# YarnControl_Driver_v1_0.net
KiCad netlist of a schematic drawn in Altium Designer
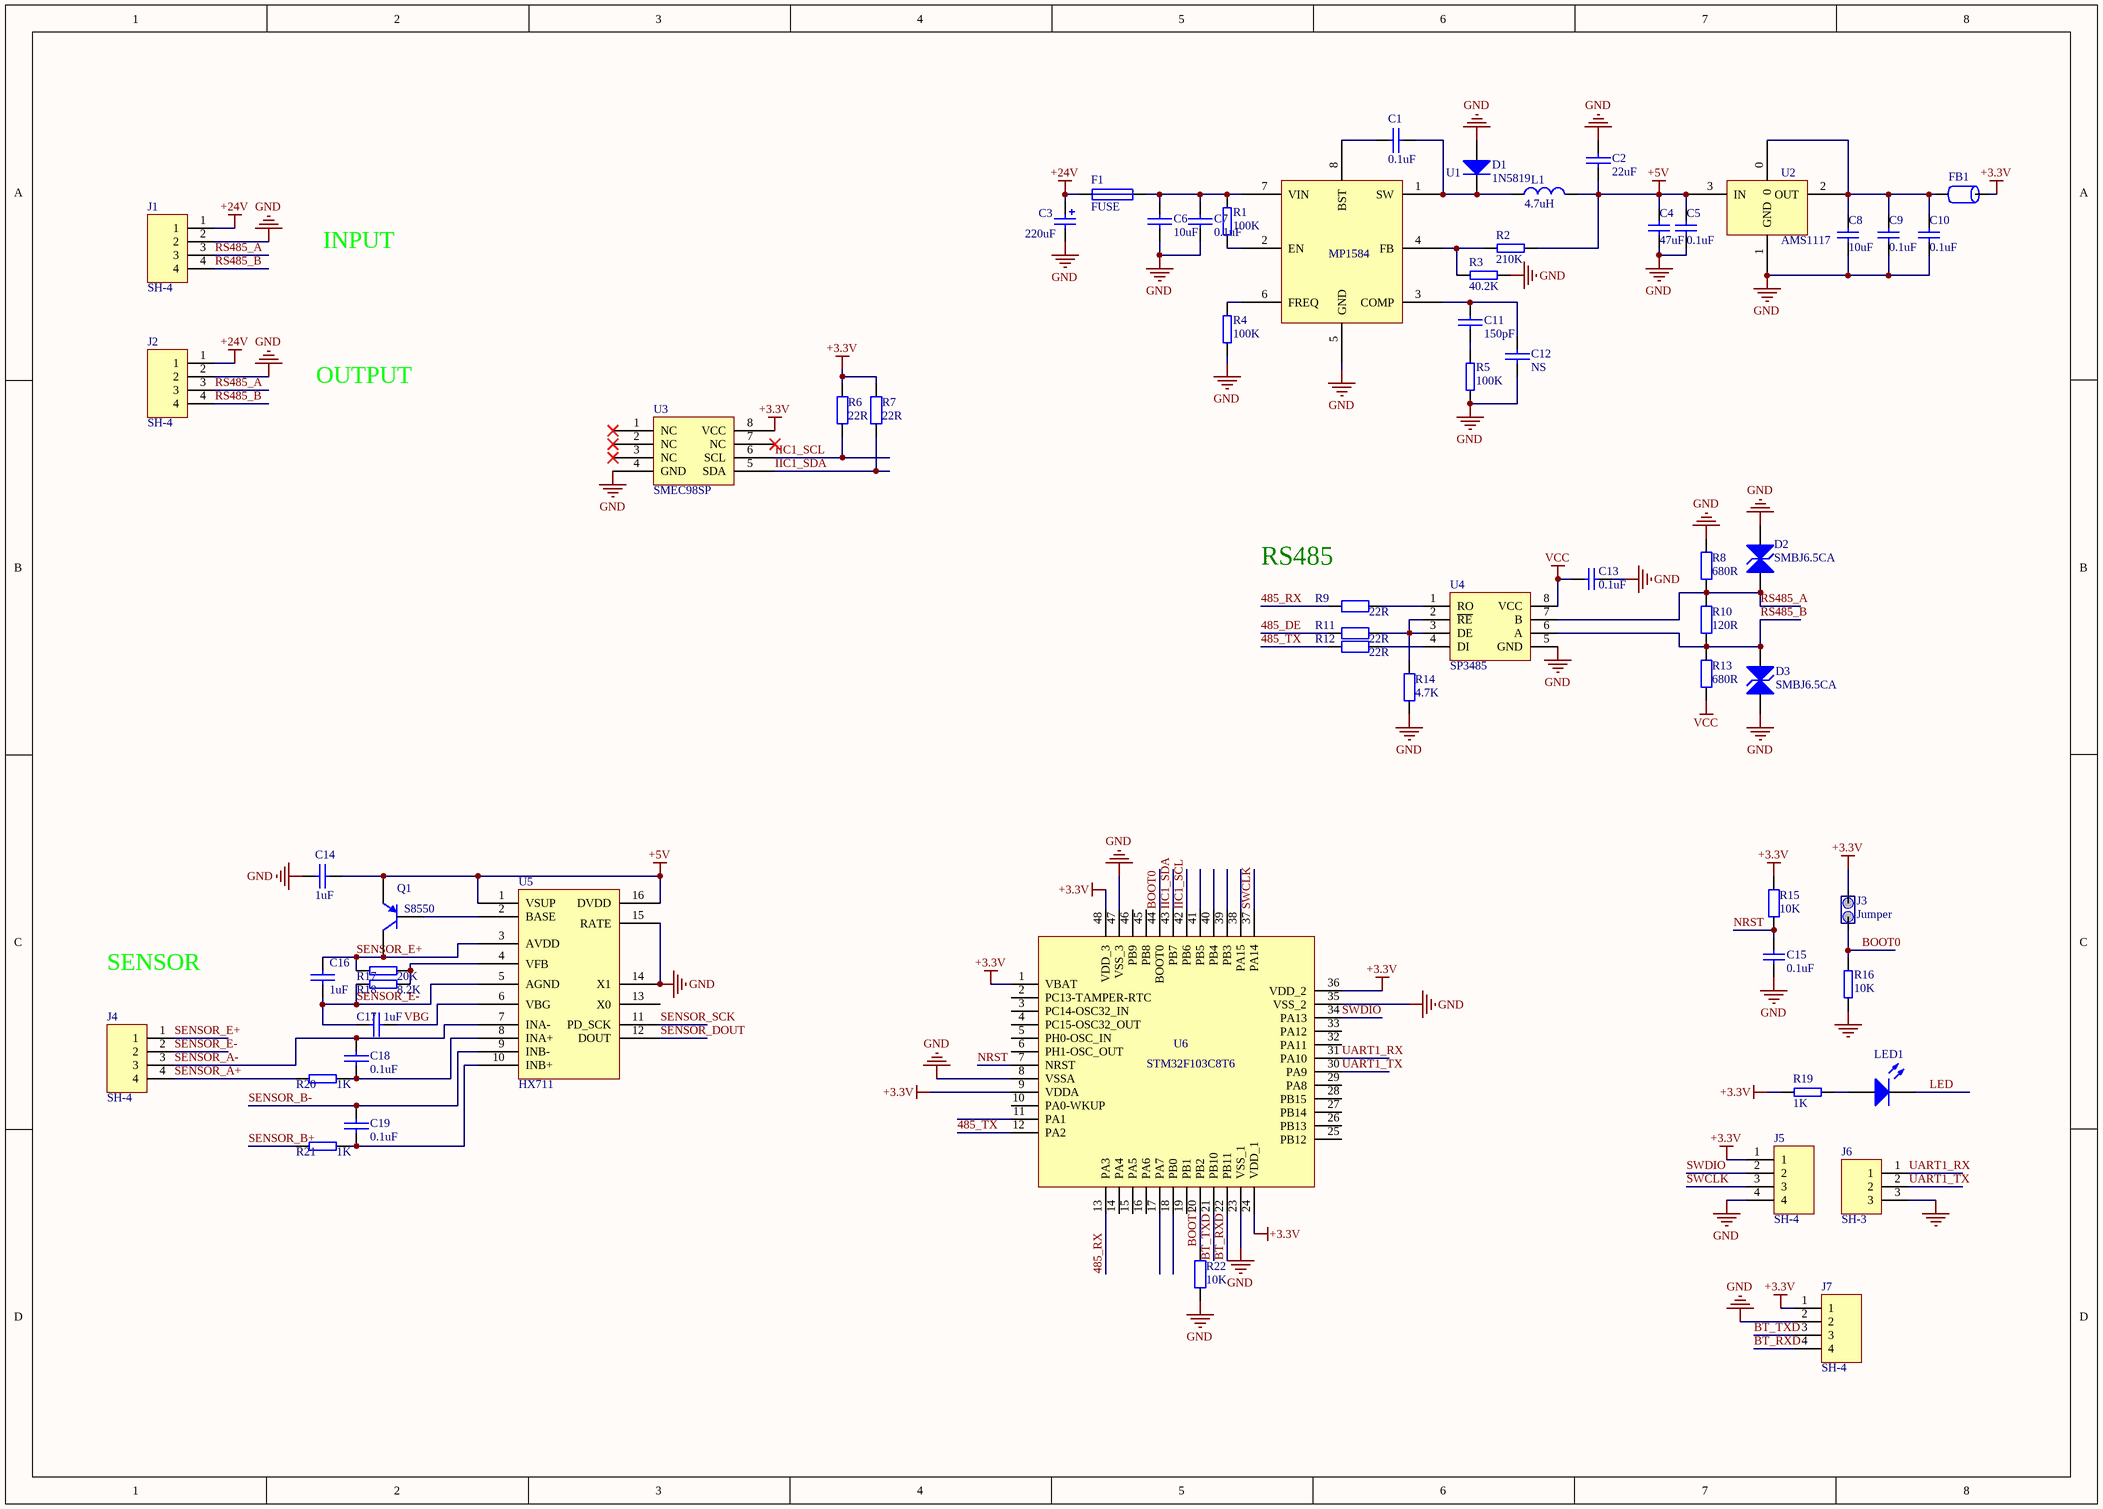
[diagram p0: YarnControl_Driver_v1.0.SchDoc]

(export (version "E")
  (design (tool "Eeschema 10.0.6"))
  (components
    (comp (ref "C1")
      (value "0.1uF")
      (footprint "0805")
      (description "电容")
      (libsource (lib "Component") (part "CAP"))
    )
    (comp (ref "C2")
      (value "22uF")
      (footprint "0805")
      (description "电容")
      (libsource (lib "Component") (part "CAP"))
    )
    (comp (ref "C3")
      (value "220uF")
      (footprint "CAP-5mm")
      (description "电解电容")
      (libsource (lib "Component") (part "Cap Pol1"))
    )
    (comp (ref "C4") (value "47uF") (footprint "1210") (libsource (lib "Componet") (part "Cap0805")))
    (comp (ref "C5") (value "0.1uF") (footprint "0805") (libsource (lib "Componet") (part "Cap0805")))
    (comp (ref "C6")
      (value "10uF")
      (footprint "0805")
      (description "电容")
      (libsource (lib "Component") (part "CAP"))
    )
    (comp (ref "C7")
      (value "0.1uF")
      (footprint "0805")
      (description "电容")
      (libsource (lib "Component") (part "CAP"))
    )
    (comp (ref "C8") (value "10uF") (footprint "0805") (libsource (lib "Componet") (part "Cap0805")))
    (comp (ref "C9") (value "0.1uF") (footprint "0805") (libsource (lib "Componet") (part "Cap0805")))
    (comp (ref "C10") (value "0.1uF") (footprint "0805") (libsource (lib "Componet") (part "Cap0805")))
    (comp (ref "C11")
      (value "150pF")
      (footprint "0805")
      (description "电容")
      (libsource (lib "Component") (part "CAP"))
    )
    (comp (ref "C12")
      (value "NS")
      (footprint "0805")
      (description "电容")
      (libsource (lib "Component") (part "CAP"))
    )
    (comp (ref "C13")
      (value "0.1uF")
      (footprint "0805")
      (description "Capacitor")
      (fields (field (name "PUBLISHER") "Altium Limited"))
      (libsource (lib "TIAN's Schlib") (part "Cap"))
    )
    (comp (ref "C14")
      (value "1uF")
      (footprint "0805")
      (description "电容")
      (libsource (lib "Component") (part "CAP"))
    )
    (comp (ref "C15")
      (value "0.1uF")
      (footprint "0805")
      (description "Capacitor")
      (fields (field (name "PUBLISHER") "Altium Limited"))
      (libsource (lib "TIAN's Schlib") (part "Cap"))
    )
    (comp (ref "C16")
      (value "1uF")
      (footprint "0805")
      (description "电容")
      (libsource (lib "Component") (part "CAP"))
    )
    (comp (ref "C17")
      (value "1uF")
      (footprint "0805")
      (description "电容")
      (libsource (lib "Component") (part "CAP"))
    )
    (comp (ref "C18")
      (value "0.1uF")
      (footprint "0805")
      (description "电容")
      (libsource (lib "Component") (part "CAP"))
    )
    (comp (ref "C19")
      (value "0.1uF")
      (footprint "0805")
      (description "电容")
      (libsource (lib "Component") (part "CAP"))
    )
    (comp (ref "D1")
      (value "1N5819")
      (footprint "Diode_TP2")
      (description "二极管")
      (fields (field (name "PUBLISHER") "Altium Limited"))
      (libsource (lib "Component") (part "Diode"))
    )
    (comp (ref "D2")
      (value "SMBJ6.5CA")
      (footprint "SMBJ_DO-214")
      (fields (field (name "PUBLISHER") "Altium Limited"))
      (libsource (lib "TIAN's Schlib") (part "TVS"))
    )
    (comp (ref "D3")
      (value "SMBJ6.5CA")
      (footprint "SMBJ_DO-214")
      (fields (field (name "PUBLISHER") "Altium Limited"))
      (libsource (lib "TIAN's Schlib") (part "TVS"))
    )
    (comp (ref "F1")
      (value "FUSE")
      (footprint "1206")
      (description "保险丝")
      (libsource (lib "Component") (part "FUSE"))
    )
    (comp (ref "FB1") (value "FERRITE") (footprint "0805") (libsource (lib "Connector") (part "FERRITE")))
    (comp (ref "J1") (value "SH-4") (footprint "J5.08_4(NoEar)") (libsource (lib "Connector") (part "SH-4")))
    (comp (ref "J2") (value "SH-4") (footprint "J5.08_4(NoEar)") (libsource (lib "Connector") (part "SH-4")))
    (comp (ref "J3") (value "Jumper") (footprint "J254-2") (libsource (lib "Connector") (part "Jumper")))
    (comp (ref "J4") (value "SH-4") (footprint "CH3.96-4P") (libsource (lib "Connector") (part "SH-4")))
    (comp (ref "J5") (value "SH-4") (footprint "J254-4") (libsource (lib "") (part "SH-4_1")))
    (comp (ref "J6") (value "SH-3") (footprint "J2.54-3") (libsource (lib "Connector") (part "SH-3")))
    (comp (ref "J7") (value "SH-4") (footprint "J254-4") (libsource (lib "") (part "SH-4_1")))
    (comp (ref "L1")
      (value "4.7uH")
      (footprint "0805")
      (description "电感")
      (libsource (lib "Component") (part "Inductor"))
    )
    (comp (ref "LED1")
      (value "GREEN")
      (footprint "LED")
      (description "Typical RED, GREEN, YELLOW, AMBER GaAs LED")
      (fields (field (name "PUBLISHER") "Altium Limited"))
      (libsource (lib "Miscellaneous Devices") (part "LED2"))
    )
    (comp (ref "Q1") (value "S8550") (footprint "901X_SOT-23") (libsource (lib "Componet") (part "PNP")))
    (comp (ref "R1")
      (value "100K")
      (footprint "0805")
      (description "电阻")
      (libsource (lib "Component") (part "RES"))
    )
    (comp (ref "R2")
      (value "210K")
      (footprint "0805")
      (description "电阻")
      (libsource (lib "Component") (part "RES"))
    )
    (comp (ref "R3")
      (value "40.2K")
      (footprint "0805")
      (description "电阻")
      (libsource (lib "Component") (part "RES"))
    )
    (comp (ref "R4")
      (value "100K")
      (footprint "0805")
      (description "电阻")
      (libsource (lib "Component") (part "RES"))
    )
    (comp (ref "R5")
      (value "100K")
      (footprint "0805")
      (description "电阻")
      (libsource (lib "Component") (part "RES"))
    )
    (comp (ref "R6")
      (value "22R")
      (footprint "0805")
      (description "Resistor")
      (fields (field (name "PUBLISHER") "Altium Limited"))
      (libsource (lib "TIAN's Schlib") (part "Res2"))
    )
    (comp (ref "R7")
      (value "22R")
      (footprint "0805")
      (description "Resistor")
      (fields (field (name "PUBLISHER") "Altium Limited"))
      (libsource (lib "TIAN's Schlib") (part "Res2"))
    )
    (comp (ref "R8")
      (value "680R")
      (footprint "0805")
      (description "Resistor")
      (fields (field (name "PUBLISHER") "Altium Limited"))
      (libsource (lib "") (part "Res2_1"))
    )
    (comp (ref "R9")
      (value "22R")
      (footprint "0805")
      (description "Resistor")
      (fields (field (name "PUBLISHER") "Altium Limited"))
      (libsource (lib "") (part "Res2_2"))
    )
    (comp (ref "R10")
      (value "120R")
      (footprint "0805")
      (description "Resistor")
      (fields (field (name "PUBLISHER") "Altium Limited"))
      (libsource (lib "") (part "Res2_1"))
    )
    (comp (ref "R11")
      (value "22R")
      (footprint "0805")
      (description "Resistor")
      (fields (field (name "PUBLISHER") "Altium Limited"))
      (libsource (lib "") (part "Res2_2"))
    )
    (comp (ref "R12")
      (value "22R")
      (footprint "0805")
      (description "Resistor")
      (fields (field (name "PUBLISHER") "Altium Limited"))
      (libsource (lib "") (part "Res2_2"))
    )
    (comp (ref "R13")
      (value "680R")
      (footprint "0805")
      (description "Resistor")
      (fields (field (name "PUBLISHER") "Altium Limited"))
      (libsource (lib "") (part "Res2_1"))
    )
    (comp (ref "R14")
      (value "4.7K")
      (footprint "0805")
      (description "Resistor")
      (fields (field (name "PUBLISHER") "Altium Limited"))
      (libsource (lib "TIAN's Schlib") (part "Res2"))
    )
    (comp (ref "R15")
      (value "10K")
      (footprint "0805")
      (description "Resistor")
      (fields (field (name "PUBLISHER") "Altium Limited"))
      (libsource (lib "TIAN's Schlib") (part "Res2"))
    )
    (comp (ref "R16")
      (value "10K")
      (footprint "0805")
      (description "电阻")
      (libsource (lib "Component") (part "RES"))
    )
    (comp (ref "R17")
      (value "20K")
      (footprint "0805")
      (description "电阻")
      (libsource (lib "Component") (part "RES"))
    )
    (comp (ref "R18")
      (value "8.2K")
      (footprint "0805")
      (description "电阻")
      (libsource (lib "Component") (part "RES"))
    )
    (comp (ref "R19")
      (value "1K")
      (footprint "0805")
      (description "电阻")
      (libsource (lib "Component") (part "RES"))
    )
    (comp (ref "R20")
      (value "1K")
      (footprint "0805")
      (description "电阻")
      (libsource (lib "Component") (part "RES"))
    )
    (comp (ref "R21")
      (value "1K")
      (footprint "0805")
      (description "电阻")
      (libsource (lib "Component") (part "RES"))
    )
    (comp (ref "R22")
      (value "10K")
      (footprint "0805")
      (description "Resistor")
      (fields (field (name "PUBLISHER") "Altium Limited"))
      (libsource (lib "TIAN's Schlib") (part "Res2"))
    )
    (comp (ref "U1") (value "MP1584") (footprint "SO-8") (libsource (lib "Chip") (part "MP1584")))
    (comp (ref "U2") (value "AMS1117") (footprint "TO-223") (libsource (lib "Chip") (part "AMS1117")))
    (comp (ref "U3") (value "SMEC98SP") (footprint "SO-8") (libsource (lib "Chip") (part "SMEC98SP")))
    (comp (ref "U4")
      (value "SP3485")
      (footprint "SO-8")
      (description "485")
      (libsource (lib "TIAN's Schlib") (part "SP3485"))
    )
    (comp (ref "U5") (value "HX711") (footprint "SO-16") (libsource (lib "Chip") (part "HX711")))
    (comp (ref "U6")
      (value "STM32F103C8T6")
      (footprint "LQFP_48")
      (libsource (lib "Chip") (part "STM32F103C8T6"))
    )
  )
  (nets
    (net (code "1") (name "+3.3V") (class "Default")
      (node (ref "FB1") (pin "2") (pinfunction "2_2") (pintype "passive"))
      (node (ref "J3") (pin "2") (pinfunction "2_2") (pintype "passive"))
      (node (ref "J5") (pin "1") (pinfunction "1_1") (pintype "passive"))
      (node (ref "J7") (pin "1") (pinfunction "1_1") (pintype "passive"))
      (node (ref "R15") (pin "2") (pinfunction "2_2") (pintype "passive"))
      (node (ref "R19") (pin "2") (pinfunction "2_2") (pintype "passive"))
      (node (ref "R6") (pin "2") (pinfunction "2_2") (pintype "passive"))
      (node (ref "R7") (pin "2") (pinfunction "2_2") (pintype "passive"))
      (node (ref "U3") (pin "8") (pinfunction "VCC_8") (pintype "passive"))
      (node (ref "U6") (pin "1") (pinfunction "VBAT_1") (pintype "passive"))
      (node (ref "U6") (pin "24") (pinfunction "VDD_1_24") (pintype "passive"))
      (node (ref "U6") (pin "36") (pinfunction "VDD_2_36") (pintype "passive"))
      (node (ref "U6") (pin "48") (pinfunction "VDD_3_48") (pintype "passive"))
      (node (ref "U6") (pin "9") (pinfunction "VDDA_9") (pintype "passive"))
    )
    (net (code "2") (name "+5V") (class "Default")
      (node (ref "C14") (pin "2") (pinfunction "2_2") (pintype "passive"))
      (node (ref "C2") (pin "2") (pinfunction "2_2") (pintype "passive"))
      (node (ref "C4") (pin "2") (pinfunction "2_2") (pintype "passive"))
      (node (ref "C5") (pin "2") (pinfunction "2_2") (pintype "passive"))
      (node (ref "L1") (pin "2") (pinfunction "2_2") (pintype "passive"))
      (node (ref "Q1") (pin "3") (pinfunction "E_3") (pintype "passive"))
      (node (ref "R2") (pin "1") (pinfunction "1_1") (pintype "passive"))
      (node (ref "U2") (pin "3") (pinfunction "IN_3") (pintype "passive"))
      (node (ref "U5") (pin "1") (pinfunction "VSUP_1") (pintype "passive"))
      (node (ref "U5") (pin "16") (pinfunction "DVDD_16") (pintype "passive"))
    )
    (net (code "3") (name "+24V") (class "Default")
      (node (ref "C3") (pin "1") (pinfunction "1_1") (pintype "passive"))
      (node (ref "F1") (pin "1") (pinfunction "1_1") (pintype "passive"))
      (node (ref "J1") (pin "1") (pinfunction "1_1") (pintype "passive"))
      (node (ref "J2") (pin "1") (pinfunction "1_1") (pintype "passive"))
    )
    (net (code "4") (name "/485_DE") (class "Default")
      (node (ref "R11") (pin "1") (pinfunction "1_1") (pintype "passive"))
    )
    (net (code "5") (name "/485_RX") (class "Default")
      (node (ref "R9") (pin "1") (pinfunction "1_1") (pintype "passive"))
      (node (ref "U6") (pin "13") (pinfunction "PA3_13") (pintype "passive"))
    )
    (net (code "6") (name "/485_TX") (class "Default")
      (node (ref "R12") (pin "1") (pinfunction "1_1") (pintype "passive"))
      (node (ref "U6") (pin "12") (pinfunction "PA2_12") (pintype "passive"))
    )
    (net (code "7") (name "/BOOT0") (class "Default")
      (node (ref "J3") (pin "1") (pinfunction "1_1") (pintype "passive"))
      (node (ref "R16") (pin "1") (pinfunction "1_1") (pintype "passive"))
      (node (ref "U6") (pin "44") (pinfunction "BOOT0_44") (pintype "passive"))
    )
    (net (code "8") (name "/BOOT1") (class "Default")
      (node (ref "R22") (pin "2") (pinfunction "2_2") (pintype "passive"))
      (node (ref "U6") (pin "20") (pinfunction "PB2_20") (pintype "passive"))
    )
    (net (code "9") (name "/BT_RXD") (class "Default")
      (node (ref "J7") (pin "4") (pinfunction "4_4") (pintype "passive"))
      (node (ref "U6") (pin "22") (pinfunction "PB11_22") (pintype "passive"))
    )
    (net (code "10") (name "/BT_TXD") (class "Default")
      (node (ref "J7") (pin "3") (pinfunction "3_3") (pintype "passive"))
      (node (ref "U6") (pin "21") (pinfunction "PB10_21") (pintype "passive"))
    )
    (net (code "11") (name "/IIC1_SCL") (class "Default")
      (node (ref "R6") (pin "1") (pinfunction "1_1") (pintype "passive"))
      (node (ref "U3") (pin "6") (pinfunction "SCL_6") (pintype "passive"))
      (node (ref "U6") (pin "42") (pinfunction "PB6_42") (pintype "passive"))
    )
    (net (code "12") (name "/IIC1_SDA") (class "Default")
      (node (ref "R7") (pin "1") (pinfunction "1_1") (pintype "passive"))
      (node (ref "U3") (pin "5") (pinfunction "SDA_5") (pintype "passive"))
      (node (ref "U6") (pin "43") (pinfunction "PB7_43") (pintype "passive"))
    )
    (net (code "13") (name "/LED") (class "Default")
      (node (ref "LED1") (pin "2") (pinfunction "K_2") (pintype "passive"))
    )
    (net (code "14") (name "/NRST") (class "Default")
      (node (ref "C15") (pin "2") (pinfunction "2_2") (pintype "passive"))
      (node (ref "R15") (pin "1") (pinfunction "1_1") (pintype "passive"))
      (node (ref "U6") (pin "7") (pinfunction "NRST_7") (pintype "passive"))
    )
    (net (code "15") (name "/RS485_A") (class "Default")
      (node (ref "D2") (pin "1") (pinfunction "A_1") (pintype "passive"))
      (node (ref "J1") (pin "3") (pinfunction "3_3") (pintype "passive"))
      (node (ref "J2") (pin "3") (pinfunction "3_3") (pintype "passive"))
      (node (ref "R10") (pin "1") (pinfunction "1_1") (pintype "passive"))
      (node (ref "R8") (pin "2") (pinfunction "2_2") (pintype "passive"))
      (node (ref "U4") (pin "7") (pinfunction "B_7") (pintype "passive"))
    )
    (net (code "16") (name "/RS485_B") (class "Default")
      (node (ref "D3") (pin "2") (pinfunction "K_2") (pintype "passive"))
      (node (ref "J1") (pin "4") (pinfunction "4_4") (pintype "passive"))
      (node (ref "J2") (pin "4") (pinfunction "4_4") (pintype "passive"))
      (node (ref "R10") (pin "2") (pinfunction "2_2") (pintype "passive"))
      (node (ref "R13") (pin "1") (pinfunction "1_1") (pintype "passive"))
      (node (ref "U4") (pin "6") (pinfunction "A_6") (pintype "passive"))
    )
    (net (code "17") (name "/SENSOR_A+") (class "Default")
      (node (ref "J4") (pin "4") (pinfunction "4_4") (pintype "passive"))
      (node (ref "R20") (pin "2") (pinfunction "2_2") (pintype "passive"))
    )
    (net (code "18") (name "/SENSOR_A-") (class "Default")
      (node (ref "C18") (pin "1") (pinfunction "1_1") (pintype "passive"))
      (node (ref "J4") (pin "3") (pinfunction "3_3") (pintype "passive"))
      (node (ref "U5") (pin "7") (pinfunction "INA-_7") (pintype "passive"))
    )
    (net (code "19") (name "/SENSOR_B+") (class "Default")
      (node (ref "R21") (pin "2") (pinfunction "2_2") (pintype "passive"))
    )
    (net (code "20") (name "/SENSOR_B-") (class "Default")
      (node (ref "C19") (pin "1") (pinfunction "1_1") (pintype "passive"))
      (node (ref "U5") (pin "9") (pinfunction "INB-_9") (pintype "passive"))
    )
    (net (code "21") (name "/SENSOR_DOUT") (class "Default")
      (node (ref "U5") (pin "12") (pinfunction "DOUT_12") (pintype "passive"))
    )
    (net (code "22") (name "/SENSOR_E+") (class "Default")
      (node (ref "C16") (pin "2") (pinfunction "2_2") (pintype "passive"))
      (node (ref "J4") (pin "1") (pinfunction "1_1") (pintype "passive"))
      (node (ref "Q1") (pin "1") (pinfunction "C_1") (pintype "passive"))
      (node (ref "R17") (pin "2") (pinfunction "2_2") (pintype "passive"))
      (node (ref "U5") (pin "3") (pinfunction "AVDD_3") (pintype "passive"))
    )
    (net (code "23") (name "/SENSOR_E-") (class "Default")
      (node (ref "C16") (pin "1") (pinfunction "1_1") (pintype "passive"))
      (node (ref "C17") (pin "2") (pinfunction "2_2") (pintype "passive"))
      (node (ref "J4") (pin "2") (pinfunction "2_2") (pintype "passive"))
      (node (ref "R18") (pin "2") (pinfunction "2_2") (pintype "passive"))
      (node (ref "U5") (pin "5") (pinfunction "AGND_5") (pintype "passive"))
    )
    (net (code "24") (name "/SENSOR_SCK") (class "Default")
      (node (ref "U5") (pin "11") (pinfunction "PD_SCK_11") (pintype "passive"))
    )
    (net (code "25") (name "/SWCLK") (class "Default")
      (node (ref "J5") (pin "3") (pinfunction "3_3") (pintype "passive"))
      (node (ref "U6") (pin "37") (pinfunction "PA14_37") (pintype "passive"))
    )
    (net (code "26") (name "/SWDIO") (class "Default")
      (node (ref "J5") (pin "2") (pinfunction "2_2") (pintype "passive"))
      (node (ref "U6") (pin "34") (pinfunction "PA13_34") (pintype "passive"))
    )
    (net (code "27") (name "/UART1_RX") (class "Default")
      (node (ref "J6") (pin "1") (pinfunction "1_1") (pintype "passive"))
      (node (ref "U6") (pin "31") (pinfunction "PA10_31") (pintype "passive"))
    )
    (net (code "28") (name "/UART1_TX") (class "Default")
      (node (ref "J6") (pin "2") (pinfunction "2_2") (pintype "passive"))
      (node (ref "U6") (pin "30") (pinfunction "PA9_30") (pintype "passive"))
    )
    (net (code "29") (name "/VBG") (class "Default")
      (node (ref "C17") (pin "1") (pinfunction "1_1") (pintype "passive"))
      (node (ref "U5") (pin "6") (pinfunction "VBG_6") (pintype "passive"))
    )
    (net (code "30") (name "GND") (class "Default")
      (node (ref "C10") (pin "1") (pinfunction "1_1") (pintype "passive"))
      (node (ref "C12") (pin "2") (pinfunction "2_2") (pintype "passive"))
      (node (ref "C13") (pin "1") (pinfunction "1_1") (pintype "passive"))
      (node (ref "C14") (pin "1") (pinfunction "1_1") (pintype "passive"))
      (node (ref "C15") (pin "1") (pinfunction "1_1") (pintype "passive"))
      (node (ref "C2") (pin "1") (pinfunction "1_1") (pintype "passive"))
      (node (ref "C3") (pin "2") (pinfunction "2_2") (pintype "passive"))
      (node (ref "C4") (pin "1") (pinfunction "1_1") (pintype "passive"))
      (node (ref "C5") (pin "1") (pinfunction "1_1") (pintype "passive"))
      (node (ref "C6") (pin "2") (pinfunction "2_2") (pintype "passive"))
      (node (ref "C7") (pin "2") (pinfunction "2_2") (pintype "passive"))
      (node (ref "C8") (pin "1") (pinfunction "1_1") (pintype "passive"))
      (node (ref "C9") (pin "1") (pinfunction "1_1") (pintype "passive"))
      (node (ref "D1") (pin "1") (pinfunction "A_1") (pintype "passive"))
      (node (ref "D2") (pin "2") (pinfunction "K_2") (pintype "passive"))
      (node (ref "D3") (pin "1") (pinfunction "A_1") (pintype "passive"))
      (node (ref "J1") (pin "2") (pinfunction "2_2") (pintype "passive"))
      (node (ref "J2") (pin "2") (pinfunction "2_2") (pintype "passive"))
      (node (ref "J5") (pin "4") (pinfunction "4_4") (pintype "passive"))
      (node (ref "J6") (pin "3") (pinfunction "3_3") (pintype "passive"))
      (node (ref "J7") (pin "2") (pinfunction "2_2") (pintype "passive"))
      (node (ref "R14") (pin "1") (pinfunction "1_1") (pintype "passive"))
      (node (ref "R16") (pin "2") (pinfunction "2_2") (pintype "passive"))
      (node (ref "R22") (pin "1") (pinfunction "1_1") (pintype "passive"))
      (node (ref "R3") (pin "1") (pinfunction "1_1") (pintype "passive"))
      (node (ref "R4") (pin "1") (pinfunction "1_1") (pintype "passive"))
      (node (ref "R5") (pin "1") (pinfunction "1_1") (pintype "passive"))
      (node (ref "R8") (pin "1") (pinfunction "1_1") (pintype "passive"))
      (node (ref "U1") (pin "5") (pinfunction "GND_5") (pintype "passive"))
      (node (ref "U2") (pin "1") (pinfunction "GND_1") (pintype "passive"))
      (node (ref "U3") (pin "4") (pinfunction "GND_4") (pintype "passive"))
      (node (ref "U4") (pin "5") (pinfunction "GND_5") (pintype "passive"))
      (node (ref "U5") (pin "14") (pinfunction "X1_14") (pintype "passive"))
      (node (ref "U5") (pin "15") (pinfunction "RATE_15") (pintype "passive"))
      (node (ref "U6") (pin "23") (pinfunction "VSS_1_23") (pintype "passive"))
      (node (ref "U6") (pin "35") (pinfunction "VSS_2_35") (pintype "passive"))
      (node (ref "U6") (pin "47") (pinfunction "VSS_3_47") (pintype "passive"))
      (node (ref "U6") (pin "8") (pinfunction "VSSA_8") (pintype "passive"))
    )
    (net (code "31") (name "Net-(C11-Pad2)") (class "Default")
      (node (ref "C11") (pin "2") (pinfunction "2_2") (pintype "passive"))
      (node (ref "R5") (pin "2") (pinfunction "2_2") (pintype "passive"))
    )
    (net (code "32") (name "Net-(D1-K)") (class "Default")
      (node (ref "C1") (pin "2") (pinfunction "2_2") (pintype "passive"))
      (node (ref "D1") (pin "2") (pinfunction "K_2") (pintype "passive"))
      (node (ref "L1") (pin "1") (pinfunction "1_1") (pintype "passive"))
      (node (ref "U1") (pin "1") (pinfunction "SW_1") (pintype "passive"))
    )
    (net (code "33") (name "Net-(LED1-A)") (class "Default")
      (node (ref "LED1") (pin "1") (pinfunction "A_1") (pintype "passive"))
      (node (ref "R19") (pin "1") (pinfunction "1_1") (pintype "passive"))
    )
    (net (code "34") (name "Net-(Q1-B)") (class "Default")
      (node (ref "Q1") (pin "2") (pinfunction "B_2") (pintype "passive"))
      (node (ref "U5") (pin "2") (pinfunction "BASE_2") (pintype "passive"))
    )
    (net (code "35") (name "Net-(U1-BST)") (class "Default")
      (node (ref "C1") (pin "1") (pinfunction "1_1") (pintype "passive"))
      (node (ref "U1") (pin "8") (pinfunction "BST_8") (pintype "passive"))
    )
    (net (code "36") (name "Net-(U1-COMP)") (class "Default")
      (node (ref "C11") (pin "1") (pinfunction "1_1") (pintype "passive"))
      (node (ref "C12") (pin "1") (pinfunction "1_1") (pintype "passive"))
      (node (ref "U1") (pin "3") (pinfunction "COMP_3") (pintype "passive"))
    )
    (net (code "37") (name "Net-(U1-EN)") (class "Default")
      (node (ref "R1") (pin "1") (pinfunction "1_1") (pintype "passive"))
      (node (ref "U1") (pin "2") (pinfunction "EN_2") (pintype "passive"))
    )
    (net (code "38") (name "Net-(U1-FB)") (class "Default")
      (node (ref "R2") (pin "2") (pinfunction "2_2") (pintype "passive"))
      (node (ref "R3") (pin "2") (pinfunction "2_2") (pintype "passive"))
      (node (ref "U1") (pin "4") (pinfunction "FB_4") (pintype "passive"))
    )
    (net (code "39") (name "Net-(U1-FREQ)") (class "Default")
      (node (ref "R4") (pin "2") (pinfunction "2_2") (pintype "passive"))
      (node (ref "U1") (pin "6") (pinfunction "FREQ_6") (pintype "passive"))
    )
    (net (code "40") (name "Net-(U1-VIN)") (class "Default")
      (node (ref "C6") (pin "1") (pinfunction "1_1") (pintype "passive"))
      (node (ref "C7") (pin "1") (pinfunction "1_1") (pintype "passive"))
      (node (ref "F1") (pin "2") (pinfunction "2_2") (pintype "passive"))
      (node (ref "R1") (pin "2") (pinfunction "2_2") (pintype "passive"))
      (node (ref "U1") (pin "7") (pinfunction "VIN_7") (pintype "passive"))
    )
    (net (code "41") (name "Net-(U2-OUT)") (class "Default")
      (node (ref "C10") (pin "2") (pinfunction "2_2") (pintype "passive"))
      (node (ref "C8") (pin "2") (pinfunction "2_2") (pintype "passive"))
      (node (ref "C9") (pin "2") (pinfunction "2_2") (pintype "passive"))
      (node (ref "FB1") (pin "1") (pinfunction "1_1") (pintype "passive"))
      (node (ref "U2") (pin "0") (pinfunction "0_0") (pintype "passive"))
      (node (ref "U2") (pin "2") (pinfunction "OUT_2") (pintype "passive"))
    )
    (net (code "42") (name "Net-(U4-DE)") (class "Default")
      (node (ref "R11") (pin "2") (pinfunction "2_2") (pintype "passive"))
      (node (ref "R14") (pin "2") (pinfunction "2_2") (pintype "passive"))
      (node (ref "U4") (pin "2") (pinfunction "~{RE}_2") (pintype "passive"))
      (node (ref "U4") (pin "3") (pinfunction "DE_3") (pintype "passive"))
    )
    (net (code "43") (name "Net-(U4-DI)") (class "Default")
      (node (ref "R12") (pin "2") (pinfunction "2_2") (pintype "passive"))
      (node (ref "U4") (pin "4") (pinfunction "DI_4") (pintype "passive"))
    )
    (net (code "44") (name "Net-(U4-RO)") (class "Default")
      (node (ref "R9") (pin "2") (pinfunction "2_2") (pintype "passive"))
      (node (ref "U4") (pin "1") (pinfunction "RO_1") (pintype "passive"))
    )
    (net (code "45") (name "Net-(U5-INA+)") (class "Default")
      (node (ref "C18") (pin "2") (pinfunction "2_2") (pintype "passive"))
      (node (ref "R20") (pin "1") (pinfunction "1_1") (pintype "passive"))
      (node (ref "U5") (pin "8") (pinfunction "INA+_8") (pintype "passive"))
    )
    (net (code "46") (name "Net-(U5-INB+)") (class "Default")
      (node (ref "C19") (pin "2") (pinfunction "2_2") (pintype "passive"))
      (node (ref "R21") (pin "1") (pinfunction "1_1") (pintype "passive"))
      (node (ref "U5") (pin "10") (pinfunction "INB+_10") (pintype "passive"))
    )
    (net (code "47") (name "Net-(U5-VFB)") (class "Default")
      (node (ref "R17") (pin "1") (pinfunction "1_1") (pintype "passive"))
      (node (ref "R18") (pin "1") (pinfunction "1_1") (pintype "passive"))
      (node (ref "U5") (pin "4") (pinfunction "VFB_4") (pintype "passive"))
    )
    (net (code "48") (name "VCC") (class "Default")
      (node (ref "C13") (pin "2") (pinfunction "2_2") (pintype "passive"))
      (node (ref "R13") (pin "2") (pinfunction "2_2") (pintype "passive"))
      (node (ref "U4") (pin "8") (pinfunction "VCC_8") (pintype "passive"))
    )
    (net (code "49") (name "unconnected-(U3-NC-Pad1)") (class "Default")
      (node (ref "U3") (pin "1") (pinfunction "NC_1") (pintype "passive+no_connect"))
    )
    (net (code "50") (name "unconnected-(U3-NC-Pad2)") (class "Default")
      (node (ref "U3") (pin "2") (pinfunction "NC_2") (pintype "passive+no_connect"))
    )
    (net (code "51") (name "unconnected-(U3-NC-Pad3)") (class "Default")
      (node (ref "U3") (pin "3") (pinfunction "NC_3") (pintype "passive+no_connect"))
    )
    (net (code "52") (name "unconnected-(U3-NC-Pad7)") (class "Default")
      (node (ref "U3") (pin "7") (pinfunction "NC_7") (pintype "passive+no_connect"))
    )
    (net (code "53") (name "unconnected-(U5-X0-Pad13)") (class "Default")
      (node (ref "U5") (pin "13") (pinfunction "X0_13") (pintype "passive"))
    )
    (net (code "54") (name "unconnected-(U6-PA0-WKUP-Pad10)") (class "Default")
      (node (ref "U6") (pin "10") (pinfunction "PA0-WKUP_10") (pintype "passive"))
    )
    (net (code "55") (name "unconnected-(U6-PA1-Pad11)") (class "Default")
      (node (ref "U6") (pin "11") (pinfunction "PA1_11") (pintype "passive"))
    )
    (net (code "56") (name "unconnected-(U6-PA4-Pad14)") (class "Default")
      (node (ref "U6") (pin "14") (pinfunction "PA4_14") (pintype "passive"))
    )
    (net (code "57") (name "unconnected-(U6-PA5-Pad15)") (class "Default")
      (node (ref "U6") (pin "15") (pinfunction "PA5_15") (pintype "passive"))
    )
    (net (code "58") (name "unconnected-(U6-PA6-Pad16)") (class "Default")
      (node (ref "U6") (pin "16") (pinfunction "PA6_16") (pintype "passive"))
    )
    (net (code "59") (name "unconnected-(U6-PA7-Pad17)") (class "Default")
      (node (ref "U6") (pin "17") (pinfunction "PA7_17") (pintype "passive"))
    )
    (net (code "60") (name "unconnected-(U6-PA8-Pad29)") (class "Default")
      (node (ref "U6") (pin "29") (pinfunction "PA8_29") (pintype "passive"))
    )
    (net (code "61") (name "unconnected-(U6-PA11-Pad32)") (class "Default")
      (node (ref "U6") (pin "32") (pinfunction "PA11_32") (pintype "passive"))
    )
    (net (code "62") (name "unconnected-(U6-PA12-Pad33)") (class "Default")
      (node (ref "U6") (pin "33") (pinfunction "PA12_33") (pintype "passive"))
    )
    (net (code "63") (name "unconnected-(U6-PA15-Pad38)") (class "Default")
      (node (ref "U6") (pin "38") (pinfunction "PA15_38") (pintype "passive"))
    )
    (net (code "64") (name "unconnected-(U6-PB0-Pad18)") (class "Default")
      (node (ref "U6") (pin "18") (pinfunction "PB0_18") (pintype "passive"))
    )
    (net (code "65") (name "unconnected-(U6-PB1-Pad19)") (class "Default")
      (node (ref "U6") (pin "19") (pinfunction "PB1_19") (pintype "passive"))
    )
    (net (code "66") (name "unconnected-(U6-PB3-Pad39)") (class "Default")
      (node (ref "U6") (pin "39") (pinfunction "PB3_39") (pintype "passive"))
    )
    (net (code "67") (name "unconnected-(U6-PB4-Pad40)") (class "Default")
      (node (ref "U6") (pin "40") (pinfunction "PB4_40") (pintype "passive"))
    )
    (net (code "68") (name "unconnected-(U6-PB5-Pad41)") (class "Default")
      (node (ref "U6") (pin "41") (pinfunction "PB5_41") (pintype "passive"))
    )
    (net (code "69") (name "unconnected-(U6-PB8-Pad45)") (class "Default")
      (node (ref "U6") (pin "45") (pinfunction "PB8_45") (pintype "passive"))
    )
    (net (code "70") (name "unconnected-(U6-PB9-Pad46)") (class "Default")
      (node (ref "U6") (pin "46") (pinfunction "PB9_46") (pintype "passive"))
    )
    (net (code "71") (name "unconnected-(U6-PB12-Pad25)") (class "Default")
      (node (ref "U6") (pin "25") (pinfunction "PB12_25") (pintype "passive"))
    )
    (net (code "72") (name "unconnected-(U6-PB13-Pad26)") (class "Default")
      (node (ref "U6") (pin "26") (pinfunction "PB13_26") (pintype "passive"))
    )
    (net (code "73") (name "unconnected-(U6-PB14-Pad27)") (class "Default")
      (node (ref "U6") (pin "27") (pinfunction "PB14_27") (pintype "passive"))
    )
    (net (code "74") (name "unconnected-(U6-PB15-Pad28)") (class "Default")
      (node (ref "U6") (pin "28") (pinfunction "PB15_28") (pintype "passive"))
    )
    (net (code "75") (name "unconnected-(U6-PC13-TAMPER-RTC-Pad2)") (class "Default")
      (node (ref "U6") (pin "2") (pinfunction "PC13-TAMPER-RTC_2") (pintype "passive"))
    )
    (net (code "76") (name "unconnected-(U6-PC14-OSC32_IN-Pad3)") (class "Default")
      (node (ref "U6") (pin "3") (pinfunction "PC14-OSC32_IN_3") (pintype "passive"))
    )
    (net (code "77") (name "unconnected-(U6-PC15-OSC32_OUT-Pad4)") (class "Default")
      (node (ref "U6") (pin "4") (pinfunction "PC15-OSC32_OUT_4") (pintype "passive"))
    )
    (net (code "78") (name "unconnected-(U6-PH0-OSC_IN-Pad5)") (class "Default")
      (node (ref "U6") (pin "5") (pinfunction "PH0-OSC_IN_5") (pintype "passive"))
    )
    (net (code "79") (name "unconnected-(U6-PH1-OSC_OUT-Pad6)") (class "Default")
      (node (ref "U6") (pin "6") (pinfunction "PH1-OSC_OUT_6") (pintype "passive"))
    )
  )
)
